# design.net
KiCad netlist of a schematic drawn in Altium Designer
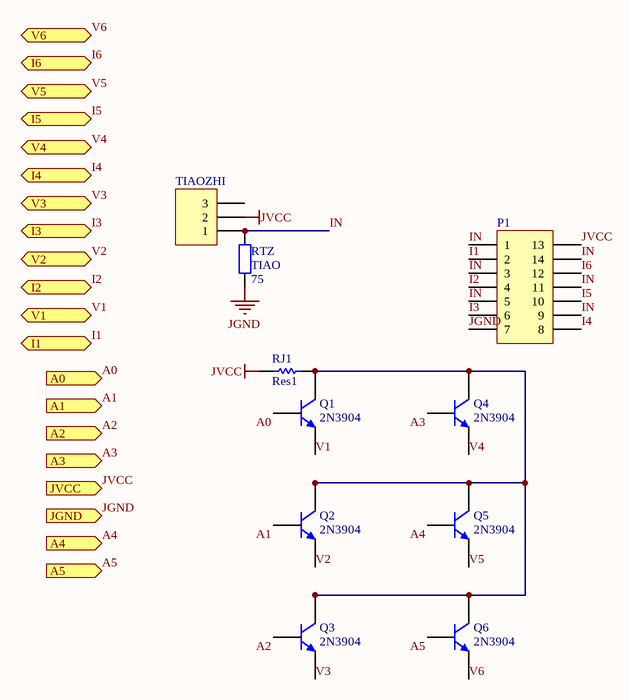
[diagram p0: 发射控制电路.SchDoc]

(export (version "E")
  (design (tool "Eeschema 10.0.6"))
  (components
    (comp (ref "P1")
      (value "Header 7X2A")
      (footprint "74LS04SOP")
      (description "Header, 7-Pin, Dual row")
      (fields (field (name "PUBLISHER") "Altium Limited"))
      (libsource (lib "Miscellaneous Connectors") (part "Header 7X2A"))
    )
    (comp (ref "Q1")
      (value "2N3904")
      (footprint "3904")
      (description "NPN General Purpose Amplifier")
      (fields (field (name "PUBLISHER") "Altium Limited"))
      (libsource (lib "Miscellaneous Devices") (part "2N3904"))
    )
    (comp (ref "Q2")
      (value "2N3904")
      (footprint "3904")
      (description "NPN General Purpose Amplifier")
      (fields (field (name "PUBLISHER") "Altium Limited"))
      (libsource (lib "Miscellaneous Devices") (part "2N3904"))
    )
    (comp (ref "Q3")
      (value "2N3904")
      (footprint "3904")
      (description "NPN General Purpose Amplifier")
      (fields (field (name "PUBLISHER") "Altium Limited"))
      (libsource (lib "Miscellaneous Devices") (part "2N3904"))
    )
    (comp (ref "Q4")
      (value "2N3904")
      (footprint "3904")
      (description "NPN General Purpose Amplifier")
      (fields (field (name "PUBLISHER") "Altium Limited"))
      (libsource (lib "Miscellaneous Devices") (part "2N3904"))
    )
    (comp (ref "Q5")
      (value "2N3904")
      (footprint "3904")
      (description "NPN General Purpose Amplifier")
      (fields (field (name "PUBLISHER") "Altium Limited"))
      (libsource (lib "Miscellaneous Devices") (part "2N3904"))
    )
    (comp (ref "Q6")
      (value "2N3904")
      (footprint "3904")
      (description "NPN General Purpose Amplifier")
      (fields (field (name "PUBLISHER") "Altium Limited"))
      (libsource (lib "Miscellaneous Devices") (part "2N3904"))
    )
    (comp (ref "RJ1")
      (value "Res1")
      (footprint "0805")
      (description "Resistor")
      (fields (field (name "PUBLISHER") "Altium Limited"))
      (libsource (lib "Miscellaneous Devices") (part "Res1"))
    )
    (comp (ref "RTZ")
      (value "TIAO")
      (footprint "0805")
      (description "Resistor")
      (fields (field (name "ALTIUM_VALUE") "75") (field (name "PUBLISHER") "Altium Limited"))
      (libsource (lib "Miscellaneous Devices") (part "Res2"))
    )
    (comp (ref "TIAOZHI")
      (value "Header 3")
      (footprint "TIAOZHI")
      (description "Header, 3-Pin")
      (fields (field (name "PUBLISHER") "Altium Limited"))
      (libsource (lib "Miscellaneous Connectors") (part "Header 3"))
    )
  )
  (nets
    (net (code "1") (name "/A0") (class "Default")
      (node (ref "Q1") (pin "2") (pinfunction "E_2") (pintype "passive"))
    )
    (net (code "2") (name "/A1") (class "Default")
      (node (ref "Q2") (pin "2") (pinfunction "E_2") (pintype "passive"))
    )
    (net (code "3") (name "/A2") (class "Default")
      (node (ref "Q3") (pin "2") (pinfunction "E_2") (pintype "passive"))
    )
    (net (code "4") (name "/A3") (class "Default")
      (node (ref "Q4") (pin "2") (pinfunction "E_2") (pintype "passive"))
    )
    (net (code "5") (name "/A4") (class "Default")
      (node (ref "Q5") (pin "2") (pinfunction "E_2") (pintype "passive"))
    )
    (net (code "6") (name "/A5") (class "Default")
      (node (ref "Q6") (pin "2") (pinfunction "E_2") (pintype "passive"))
    )
    (net (code "7") (name "/I1") (class "Default")
      (node (ref "P1") (pin "2") (pinfunction "2_2") (pintype "passive"))
    )
    (net (code "8") (name "/I2") (class "Default")
      (node (ref "P1") (pin "4") (pinfunction "4_4") (pintype "passive"))
    )
    (net (code "9") (name "/I3") (class "Default")
      (node (ref "P1") (pin "6") (pinfunction "6_6") (pintype "passive"))
    )
    (net (code "10") (name "/I4") (class "Default")
      (node (ref "P1") (pin "8") (pinfunction "8_8") (pintype "passive"))
    )
    (net (code "11") (name "/I5") (class "Default")
      (node (ref "P1") (pin "10") (pinfunction "10_10") (pintype "passive"))
    )
    (net (code "12") (name "/I6") (class "Default")
      (node (ref "P1") (pin "12") (pinfunction "12_12") (pintype "passive"))
    )
    (net (code "13") (name "/IN") (class "Default")
      (node (ref "P1") (pin "1") (pinfunction "1_1") (pintype "passive"))
      (node (ref "P1") (pin "11") (pinfunction "11_11") (pintype "passive"))
      (node (ref "P1") (pin "13") (pinfunction "14_13") (pintype "passive"))
      (node (ref "P1") (pin "3") (pinfunction "3_3") (pintype "passive"))
      (node (ref "P1") (pin "5") (pinfunction "5_5") (pintype "passive"))
      (node (ref "P1") (pin "9") (pinfunction "9_9") (pintype "passive"))
      (node (ref "RTZ") (pin "2") (pinfunction "2_2") (pintype "passive"))
      (node (ref "TIAOZHI") (pin "1") (pinfunction "1_1") (pintype "passive"))
    )
    (net (code "14") (name "/V1") (class "Default")
      (node (ref "Q1") (pin "1") (pinfunction "B_1") (pintype "passive"))
    )
    (net (code "15") (name "/V2") (class "Default")
      (node (ref "Q2") (pin "1") (pinfunction "B_1") (pintype "passive"))
    )
    (net (code "16") (name "/V3") (class "Default")
      (node (ref "Q3") (pin "1") (pinfunction "B_1") (pintype "passive"))
    )
    (net (code "17") (name "/V4") (class "Default")
      (node (ref "Q4") (pin "1") (pinfunction "B_1") (pintype "passive"))
    )
    (net (code "18") (name "/V5") (class "Default")
      (node (ref "Q5") (pin "1") (pinfunction "B_1") (pintype "passive"))
    )
    (net (code "19") (name "/V6") (class "Default")
      (node (ref "Q6") (pin "1") (pinfunction "B_1") (pintype "passive"))
    )
    (net (code "20") (name "JGND") (class "Default")
      (node (ref "P1") (pin "7") (pinfunction "7_7") (pintype "passive"))
      (node (ref "RTZ") (pin "1") (pinfunction "1_1") (pintype "passive"))
    )
    (net (code "21") (name "JVCC") (class "Default")
      (node (ref "P1") (pin "14") (pinfunction "13_14") (pintype "passive"))
      (node (ref "RJ1") (pin "1") (pinfunction "1_1") (pintype "passive"))
      (node (ref "TIAOZHI") (pin "2") (pinfunction "2_2") (pintype "passive"))
    )
    (net (code "22") (name "Net-(Q1-C)") (class "Default")
      (node (ref "Q1") (pin "3") (pinfunction "C_3") (pintype "passive"))
      (node (ref "Q2") (pin "3") (pinfunction "C_3") (pintype "passive"))
      (node (ref "Q3") (pin "3") (pinfunction "C_3") (pintype "passive"))
      (node (ref "Q4") (pin "3") (pinfunction "C_3") (pintype "passive"))
      (node (ref "Q5") (pin "3") (pinfunction "C_3") (pintype "passive"))
      (node (ref "Q6") (pin "3") (pinfunction "C_3") (pintype "passive"))
      (node (ref "RJ1") (pin "2") (pinfunction "2_2") (pintype "passive"))
    )
    (net (code "23") (name "unconnected-(TIAOZHI-Pad3)") (class "Default")
      (node (ref "TIAOZHI") (pin "3") (pinfunction "3_3") (pintype "passive"))
    )
  )
)
